# Servotor32.net
KiCad netlist of a schematic drawn in EAGLE
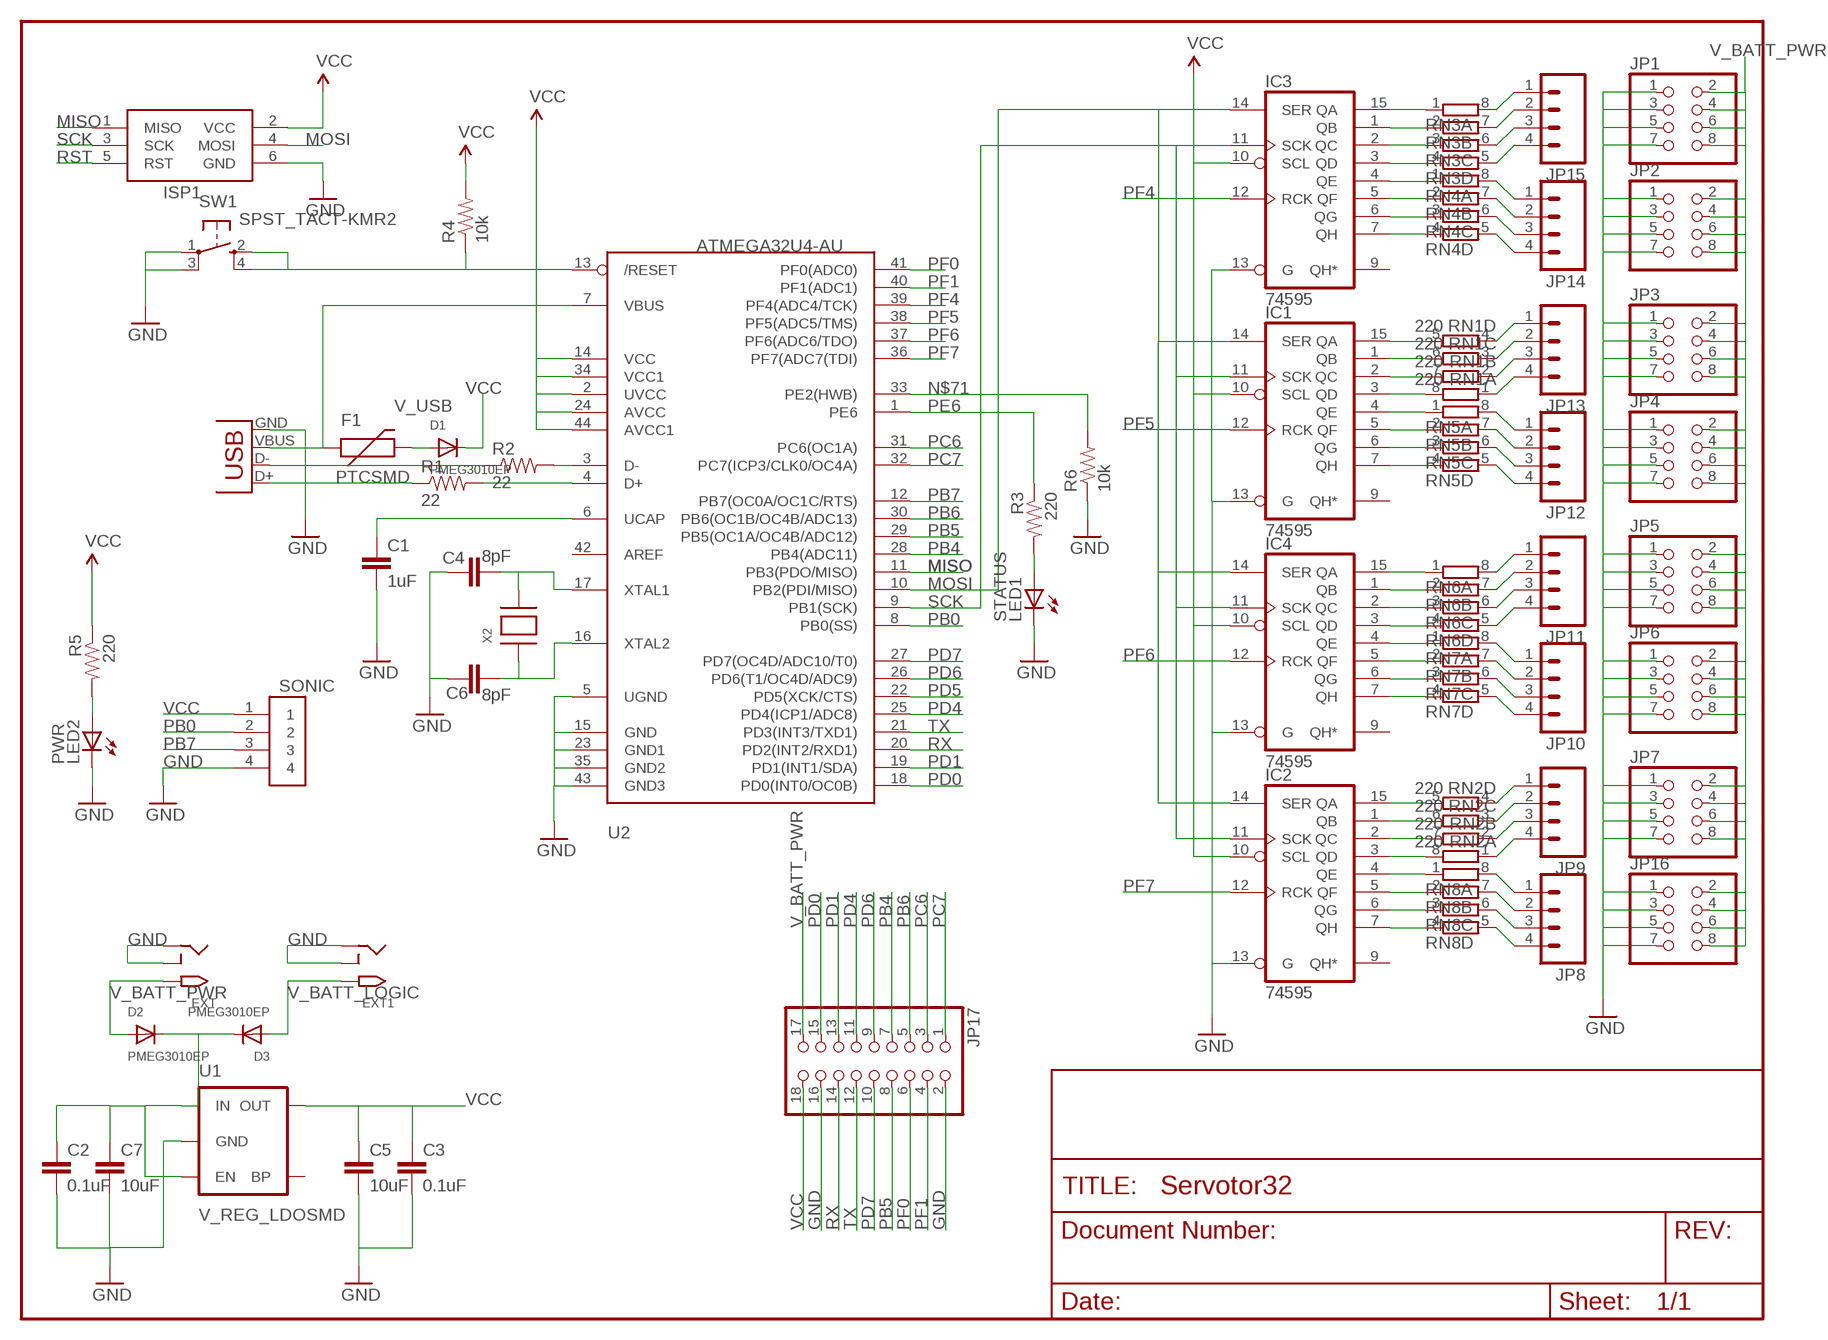
[diagram p0: schematic, sheet 1]

(export (version "E")
  (design (tool "Eeschema 10.0.6"))
  (components
    (comp (ref "C1")
      (value "1uF")
      (footprint "eagle-import:0603-CAP")
      (libsource (lib "eagle-import") (part "CAP0603-CAP"))
    )
    (comp (ref "C2")
      (value "0.1uF")
      (footprint "eagle-import:0603-CAP")
      (libsource (lib "eagle-import") (part "CAP0603-CAP"))
    )
    (comp (ref "C3")
      (value "0.1uF")
      (footprint "eagle-import:0603-CAP")
      (libsource (lib "eagle-import") (part "CAP0603-CAP"))
    )
    (comp (ref "C4")
      (value "8pF")
      (footprint "eagle-import:0603-CAP")
      (libsource (lib "eagle-import") (part "CAP0603-CAP"))
    )
    (comp (ref "C5")
      (value "10uF")
      (footprint "eagle-import:0805")
      (libsource (lib "eagle-import") (part "CAP0805"))
    )
    (comp (ref "C6")
      (value "8pF")
      (footprint "eagle-import:0603-CAP")
      (libsource (lib "eagle-import") (part "CAP0603-CAP"))
    )
    (comp (ref "C7")
      (value "10uF")
      (footprint "eagle-import:0805")
      (libsource (lib "eagle-import") (part "CAP0805"))
    )
    (comp (ref "D1")
      (value "PMEG3010EP")
      (footprint "eagle-import:SOD-128")
      (libsource (lib "eagle-import") (part "PMEG3010EP"))
    )
    (comp (ref "D2")
      (value "PMEG3010EP")
      (footprint "eagle-import:SOD-128")
      (libsource (lib "eagle-import") (part "PMEG3010EP"))
    )
    (comp (ref "D3")
      (value "PMEG3010EP")
      (footprint "eagle-import:SOD-128")
      (libsource (lib "eagle-import") (part "PMEG3010EP"))
    )
    (comp (ref "EXT")
      (value "2.1MMJACKTHM")
      (footprint "eagle-import:PJ-102A")
      (libsource (lib "eagle-import") (part "2.1MMJACKTHM"))
    )
    (comp (ref "EXT1")
      (value "2.1MMJACKTHM")
      (footprint "eagle-import:PJ-102A")
      (libsource (lib "eagle-import") (part "2.1MMJACKTHM"))
    )
    (comp (ref "F1")
      (value "PTCSMD")
      (footprint "eagle-import:PTC-1206")
      (libsource (lib "eagle-import") (part "PTCSMD"))
    )
    (comp (ref "IC1")
      (value "74595")
      (footprint "eagle-import:TSSOP16")
      (libsource (lib "eagle-import") (part "74595"))
    )
    (comp (ref "IC2")
      (value "74595")
      (footprint "eagle-import:TSSOP16")
      (libsource (lib "eagle-import") (part "74595"))
    )
    (comp (ref "IC3")
      (value "74595")
      (footprint "eagle-import:TSSOP16")
      (libsource (lib "eagle-import") (part "74595"))
    )
    (comp (ref "IC4")
      (value "74595")
      (footprint "eagle-import:TSSOP16")
      (libsource (lib "eagle-import") (part "74595"))
    )
    (comp (ref "ISP1")
      (value "AVRISP-6")
      (footprint "eagle-import:AVRISP")
      (libsource (lib "eagle-import") (part "AVRISP-6"))
    )
    (comp (ref "JP1")
      (value "PINHD-2X4")
      (footprint "eagle-import:2X04")
      (libsource (lib "eagle-import") (part "PINHD-2X4"))
    )
    (comp (ref "JP2")
      (value "PINHD-2X4")
      (footprint "eagle-import:2X04")
      (libsource (lib "eagle-import") (part "PINHD-2X4"))
    )
    (comp (ref "JP3")
      (value "PINHD-2X4")
      (footprint "eagle-import:2X04")
      (libsource (lib "eagle-import") (part "PINHD-2X4"))
    )
    (comp (ref "JP4")
      (value "PINHD-2X4")
      (footprint "eagle-import:2X04")
      (libsource (lib "eagle-import") (part "PINHD-2X4"))
    )
    (comp (ref "JP5")
      (value "PINHD-2X4")
      (footprint "eagle-import:2X04")
      (libsource (lib "eagle-import") (part "PINHD-2X4"))
    )
    (comp (ref "JP6")
      (value "PINHD-2X4")
      (footprint "eagle-import:2X04")
      (libsource (lib "eagle-import") (part "PINHD-2X4"))
    )
    (comp (ref "JP7")
      (value "PINHD-2X4")
      (footprint "eagle-import:2X04")
      (libsource (lib "eagle-import") (part "PINHD-2X4"))
    )
    (comp (ref "JP8")
      (value "M04PTH")
      (footprint "eagle-import:1X04")
      (libsource (lib "eagle-import") (part "M04PTH"))
    )
    (comp (ref "JP9")
      (value "M04PTH")
      (footprint "eagle-import:1X04")
      (libsource (lib "eagle-import") (part "M04PTH"))
    )
    (comp (ref "JP10")
      (value "M04PTH")
      (footprint "eagle-import:1X04")
      (libsource (lib "eagle-import") (part "M04PTH"))
    )
    (comp (ref "JP11")
      (value "M04PTH")
      (footprint "eagle-import:1X04")
      (libsource (lib "eagle-import") (part "M04PTH"))
    )
    (comp (ref "JP12")
      (value "M04PTH")
      (footprint "eagle-import:1X04")
      (libsource (lib "eagle-import") (part "M04PTH"))
    )
    (comp (ref "JP13")
      (value "M04PTH")
      (footprint "eagle-import:1X04")
      (libsource (lib "eagle-import") (part "M04PTH"))
    )
    (comp (ref "JP14")
      (value "M04PTH")
      (footprint "eagle-import:1X04")
      (libsource (lib "eagle-import") (part "M04PTH"))
    )
    (comp (ref "JP15")
      (value "M04PTH")
      (footprint "eagle-import:1X04")
      (libsource (lib "eagle-import") (part "M04PTH"))
    )
    (comp (ref "JP16")
      (value "PINHD-2X4")
      (footprint "eagle-import:2X04")
      (libsource (lib "eagle-import") (part "PINHD-2X4"))
    )
    (comp (ref "JP17")
      (value "PINHD-2X9-BIG")
      (footprint "eagle-import:2X09-BIG")
      (libsource (lib "eagle-import") (part "PINHD-2X9-BIG"))
    )
    (comp (ref "LED1")
      (value "STATUS")
      (footprint "eagle-import:SML0805")
      (libsource (lib "eagle-import") (part "LEDSML0805"))
    )
    (comp (ref "LED2")
      (value "PWR")
      (footprint "eagle-import:SML0805")
      (libsource (lib "eagle-import") (part "LEDSML0805"))
    )
    (comp (ref "R1")
      (value "22")
      (footprint "eagle-import:0603-RES")
      (libsource (lib "eagle-import") (part "RESISTOR0603-RES"))
    )
    (comp (ref "R2")
      (value "22")
      (footprint "eagle-import:0603-RES")
      (libsource (lib "eagle-import") (part "RESISTOR0603-RES"))
    )
    (comp (ref "R3")
      (value "220")
      (footprint "eagle-import:0603-RES")
      (libsource (lib "eagle-import") (part "RESISTOR0603-RES"))
    )
    (comp (ref "R4")
      (value "10k")
      (footprint "eagle-import:0603-RES")
      (libsource (lib "eagle-import") (part "RESISTOR0603-RES"))
    )
    (comp (ref "R5")
      (value "220")
      (footprint "eagle-import:0603-RES")
      (libsource (lib "eagle-import") (part "RESISTOR0603-RES"))
    )
    (comp (ref "R6")
      (value "10k")
      (footprint "eagle-import:0603-RES")
      (libsource (lib "eagle-import") (part "RESISTOR0603-RES"))
    )
    (comp (ref "RN1")
      (value "220")
      (footprint "eagle-import:EXB38V")
      (libsource (lib "eagle-import") (part "4R-NEXB38V"))
    )
    (comp (ref "RN2")
      (value "220")
      (footprint "eagle-import:EXB38V")
      (libsource (lib "eagle-import") (part "4R-NEXB38V"))
    )
    (comp (ref "RN3")
      (value "4R-NEXB38V")
      (footprint "eagle-import:EXB38V")
      (libsource (lib "eagle-import") (part "4R-NEXB38V"))
    )
    (comp (ref "RN4")
      (value "4R-NEXB38V")
      (footprint "eagle-import:EXB38V")
      (libsource (lib "eagle-import") (part "4R-NEXB38V"))
    )
    (comp (ref "RN5")
      (value "4R-NEXB38V")
      (footprint "eagle-import:EXB38V")
      (libsource (lib "eagle-import") (part "4R-NEXB38V"))
    )
    (comp (ref "RN6")
      (value "4R-NEXB38V")
      (footprint "eagle-import:EXB38V")
      (libsource (lib "eagle-import") (part "4R-NEXB38V"))
    )
    (comp (ref "RN7")
      (value "4R-NEXB38V")
      (footprint "eagle-import:EXB38V")
      (libsource (lib "eagle-import") (part "4R-NEXB38V"))
    )
    (comp (ref "RN8")
      (value "4R-NEXB38V")
      (footprint "eagle-import:EXB38V")
      (libsource (lib "eagle-import") (part "4R-NEXB38V"))
    )
    (comp (ref "SONIC")
      (value "SONIC")
      (footprint "eagle-import:1X04-BIG")
      (libsource (lib "eagle-import") (part "1X4-BIG"))
    )
    (comp (ref "SW1")
      (value "SPST_TACT-KMR2")
      (footprint "eagle-import:KMR2")
      (libsource (lib "eagle-import") (part "SPST_TACT-KMR2"))
    )
    (comp (ref "U1")
      (value "V_REG_LDOSMD")
      (footprint "eagle-import:SOT23-5")
      (libsource (lib "eagle-import") (part "V_REG_LDOSMD"))
    )
    (comp (ref "U2")
      (value "ATMEGA32U4-AU")
      (footprint "eagle-import:TQFP44")
      (libsource (lib "eagle-import") (part "ATMEGA32U4-AU"))
    )
    (comp (ref "X1")
      (value "USBSMD")
      (footprint "eagle-import:USB-MINIB")
      (libsource (lib "eagle-import") (part "USBSMD"))
    )
    (comp (ref "X2")
      (value "XTALNX5032")
      (footprint "eagle-import:NX5032")
      (libsource (lib "eagle-import") (part "XTALNX5032"))
    )
  )
  (nets
    (net (code "1") (name "/MISO") (class "Default")
      (node (ref "ISP1") (pin "1") (pinfunction "MISO_1") (pintype "input"))
      (node (ref "U2") (pin "11") (pinfunction "PB3(PDO/MISO)_11") (pintype "bidirectional"))
    )
    (net (code "2") (name "/MOSI") (class "Default")
      (node (ref "IC1") (pin "14") (pinfunction "SER_14") (pintype "input"))
      (node (ref "IC2") (pin "14") (pinfunction "SER_14") (pintype "input"))
      (node (ref "IC3") (pin "14") (pinfunction "SER_14") (pintype "input"))
      (node (ref "IC4") (pin "14") (pinfunction "SER_14") (pintype "input"))
      (node (ref "ISP1") (pin "4") (pinfunction "MOSI_4") (pintype "output"))
      (node (ref "U2") (pin "10") (pinfunction "PB2(PDI/MISO)_10") (pintype "bidirectional"))
    )
    (net (code "3") (name "/N$71") (class "Default")
      (node (ref "R6") (pin "2") (pinfunction "2_2") (pintype "passive"))
      (node (ref "U2") (pin "33") (pinfunction "PE2(HWB)_33") (pintype "bidirectional"))
    )
    (net (code "4") (name "/PB0") (class "Default")
      (node (ref "SONIC") (pin "2") (pinfunction "2_2") (pintype "bidirectional"))
      (node (ref "U2") (pin "8") (pinfunction "PB0(SS)_8") (pintype "bidirectional"))
    )
    (net (code "5") (name "/PB4") (class "Default")
      (node (ref "JP17") (pin "7") (pinfunction "7_7") (pintype "passive"))
      (node (ref "U2") (pin "28") (pinfunction "PB4(ADC11)_28") (pintype "bidirectional"))
    )
    (net (code "6") (name "/PB5") (class "Default")
      (node (ref "JP17") (pin "8") (pinfunction "8_8") (pintype "passive"))
      (node (ref "U2") (pin "29") (pinfunction "PB5(OC1A/OC4B/ADC12)_29") (pintype "bidirectional"))
    )
    (net (code "7") (name "/PB6") (class "Default")
      (node (ref "JP17") (pin "5") (pinfunction "5_5") (pintype "passive"))
      (node (ref "U2") (pin "30") (pinfunction "PB6(OC1B/OC4B/ADC13)_30") (pintype "bidirectional"))
    )
    (net (code "8") (name "/PB7") (class "Default")
      (node (ref "SONIC") (pin "3") (pinfunction "3_3") (pintype "bidirectional"))
      (node (ref "U2") (pin "12") (pinfunction "PB7(OC0A/OC1C/RTS)_12") (pintype "bidirectional"))
    )
    (net (code "9") (name "/PC6") (class "Default")
      (node (ref "JP17") (pin "3") (pinfunction "3_3") (pintype "passive"))
      (node (ref "U2") (pin "31") (pinfunction "PC6(OC1A)_31") (pintype "bidirectional"))
    )
    (net (code "10") (name "/PC7") (class "Default")
      (node (ref "JP17") (pin "1") (pinfunction "1_1") (pintype "passive"))
      (node (ref "U2") (pin "32") (pinfunction "PC7(ICP3/CLK0/OC4A)_32") (pintype "bidirectional"))
    )
    (net (code "11") (name "/PD0") (class "Default")
      (node (ref "JP17") (pin "15") (pinfunction "15_15") (pintype "passive"))
      (node (ref "U2") (pin "18") (pinfunction "PD0(INT0/OC0B)_18") (pintype "bidirectional"))
    )
    (net (code "12") (name "/PD1") (class "Default")
      (node (ref "JP17") (pin "13") (pinfunction "13_13") (pintype "passive"))
      (node (ref "U2") (pin "19") (pinfunction "PD1(INT1/SDA)_19") (pintype "bidirectional"))
    )
    (net (code "13") (name "/PD4") (class "Default")
      (node (ref "JP17") (pin "11") (pinfunction "11_11") (pintype "passive"))
      (node (ref "U2") (pin "25") (pinfunction "PD4(ICP1/ADC8)_25") (pintype "bidirectional"))
    )
    (net (code "14") (name "/PD5") (class "Default")
      (node (ref "U2") (pin "22") (pinfunction "PD5(XCK/CTS)_22") (pintype "bidirectional"))
    )
    (net (code "15") (name "/PD6") (class "Default")
      (node (ref "JP17") (pin "9") (pinfunction "9_9") (pintype "passive"))
      (node (ref "U2") (pin "26") (pinfunction "PD6(T1/OC4D/ADC9)_26") (pintype "bidirectional"))
    )
    (net (code "16") (name "/PD7") (class "Default")
      (node (ref "JP17") (pin "10") (pinfunction "10_10") (pintype "passive"))
      (node (ref "U2") (pin "27") (pinfunction "PD7(OC4D/ADC10/T0)_27") (pintype "bidirectional"))
    )
    (net (code "17") (name "/PE6") (class "Default")
      (node (ref "R3") (pin "1") (pinfunction "1_1") (pintype "passive"))
      (node (ref "U2") (pin "1") (pinfunction "PE6_1") (pintype "bidirectional"))
    )
    (net (code "18") (name "/PF0") (class "Default")
      (node (ref "JP17") (pin "6") (pinfunction "6_6") (pintype "passive"))
      (node (ref "U2") (pin "41") (pinfunction "PF0(ADC0)_41") (pintype "bidirectional"))
    )
    (net (code "19") (name "/PF1") (class "Default")
      (node (ref "JP17") (pin "4") (pinfunction "4_4") (pintype "passive"))
      (node (ref "U2") (pin "40") (pinfunction "PF1(ADC1)_40") (pintype "bidirectional"))
    )
    (net (code "20") (name "/PF4") (class "Default")
      (node (ref "IC3") (pin "12") (pinfunction "RCK_12") (pintype "input"))
      (node (ref "U2") (pin "39") (pinfunction "PF4(ADC4/TCK)_39") (pintype "bidirectional"))
    )
    (net (code "21") (name "/PF5") (class "Default")
      (node (ref "IC1") (pin "12") (pinfunction "RCK_12") (pintype "input"))
      (node (ref "U2") (pin "38") (pinfunction "PF5(ADC5/TMS)_38") (pintype "bidirectional"))
    )
    (net (code "22") (name "/PF6") (class "Default")
      (node (ref "IC4") (pin "12") (pinfunction "RCK_12") (pintype "input"))
      (node (ref "U2") (pin "37") (pinfunction "PF6(ADC6/TDO)_37") (pintype "bidirectional"))
    )
    (net (code "23") (name "/PF7") (class "Default")
      (node (ref "IC2") (pin "12") (pinfunction "RCK_12") (pintype "input"))
      (node (ref "U2") (pin "36") (pinfunction "PF7(ADC7(TDI)_36") (pintype "bidirectional"))
    )
    (net (code "24") (name "/RST") (class "Default")
      (node (ref "ISP1") (pin "5") (pinfunction "RST_5") (pintype "output"))
      (node (ref "R4") (pin "1") (pinfunction "1_1") (pintype "passive"))
      (node (ref "SW1") (pin "2") (pinfunction "S_2") (pintype "passive"))
      (node (ref "SW1") (pin "4") (pinfunction "S1_4") (pintype "passive"))
      (node (ref "U2") (pin "13") (pinfunction "/RESET_13") (pintype "bidirectional"))
    )
    (net (code "25") (name "/RX") (class "Default")
      (node (ref "JP17") (pin "14") (pinfunction "14_14") (pintype "passive"))
      (node (ref "U2") (pin "20") (pinfunction "PD2(INT2/RXD1)_20") (pintype "bidirectional"))
    )
    (net (code "26") (name "/SCK") (class "Default")
      (node (ref "IC1") (pin "11") (pinfunction "SCK_11") (pintype "input"))
      (node (ref "IC2") (pin "11") (pinfunction "SCK_11") (pintype "input"))
      (node (ref "IC3") (pin "11") (pinfunction "SCK_11") (pintype "input"))
      (node (ref "IC4") (pin "11") (pinfunction "SCK_11") (pintype "input"))
      (node (ref "ISP1") (pin "3") (pinfunction "SCK_3") (pintype "output"))
      (node (ref "U2") (pin "9") (pinfunction "PB1(SCK)_9") (pintype "bidirectional"))
    )
    (net (code "27") (name "/TX") (class "Default")
      (node (ref "JP17") (pin "12") (pinfunction "12_12") (pintype "passive"))
      (node (ref "U2") (pin "21") (pinfunction "PD3(INT3/TXD1)_21") (pintype "bidirectional"))
    )
    (net (code "28") (name "/V_BATT") (class "Default")
      (node (ref "C2") (pin "1") (pinfunction "1_1") (pintype "passive"))
      (node (ref "C7") (pin "1") (pinfunction "1_1") (pintype "passive"))
      (node (ref "D2") (pin "P$1") (pinfunction "C_P$1") (pintype "passive"))
      (node (ref "D3") (pin "P$1") (pinfunction "C_P$1") (pintype "passive"))
      (node (ref "U1") (pin "1") (pinfunction "IN_1") (pintype "input"))
      (node (ref "U1") (pin "3") (pinfunction "EN_3") (pintype "input"))
    )
    (net (code "29") (name "/V_BATT_LOGIC") (class "Default")
      (node (ref "D3") (pin "P$2") (pinfunction "A_P$2") (pintype "passive"))
      (node (ref "EXT1") (pin "TIP") (pinfunction "TIP_TIP") (pintype "bidirectional"))
    )
    (net (code "30") (name "/V_BATT_PWR") (class "Default")
      (node (ref "D2") (pin "P$2") (pinfunction "A_P$2") (pintype "passive"))
      (node (ref "EXT") (pin "TIP") (pinfunction "TIP_TIP") (pintype "bidirectional"))
      (node (ref "JP1") (pin "2") (pinfunction "2_2") (pintype "passive"))
      (node (ref "JP1") (pin "4") (pinfunction "4_4") (pintype "passive"))
      (node (ref "JP1") (pin "6") (pinfunction "6_6") (pintype "passive"))
      (node (ref "JP1") (pin "8") (pinfunction "8_8") (pintype "passive"))
      (node (ref "JP16") (pin "2") (pinfunction "2_2") (pintype "passive"))
      (node (ref "JP16") (pin "4") (pinfunction "4_4") (pintype "passive"))
      (node (ref "JP16") (pin "6") (pinfunction "6_6") (pintype "passive"))
      (node (ref "JP16") (pin "8") (pinfunction "8_8") (pintype "passive"))
      (node (ref "JP17") (pin "17") (pinfunction "17_17") (pintype "passive"))
      (node (ref "JP2") (pin "2") (pinfunction "2_2") (pintype "passive"))
      (node (ref "JP2") (pin "4") (pinfunction "4_4") (pintype "passive"))
      (node (ref "JP2") (pin "6") (pinfunction "6_6") (pintype "passive"))
      (node (ref "JP2") (pin "8") (pinfunction "8_8") (pintype "passive"))
      (node (ref "JP3") (pin "2") (pinfunction "2_2") (pintype "passive"))
      (node (ref "JP3") (pin "4") (pinfunction "4_4") (pintype "passive"))
      (node (ref "JP3") (pin "6") (pinfunction "6_6") (pintype "passive"))
      (node (ref "JP3") (pin "8") (pinfunction "8_8") (pintype "passive"))
      (node (ref "JP4") (pin "2") (pinfunction "2_2") (pintype "passive"))
      (node (ref "JP4") (pin "4") (pinfunction "4_4") (pintype "passive"))
      (node (ref "JP4") (pin "6") (pinfunction "6_6") (pintype "passive"))
      (node (ref "JP4") (pin "8") (pinfunction "8_8") (pintype "passive"))
      (node (ref "JP5") (pin "2") (pinfunction "2_2") (pintype "passive"))
      (node (ref "JP5") (pin "4") (pinfunction "4_4") (pintype "passive"))
      (node (ref "JP5") (pin "6") (pinfunction "6_6") (pintype "passive"))
      (node (ref "JP5") (pin "8") (pinfunction "8_8") (pintype "passive"))
      (node (ref "JP6") (pin "2") (pinfunction "2_2") (pintype "passive"))
      (node (ref "JP6") (pin "4") (pinfunction "4_4") (pintype "passive"))
      (node (ref "JP6") (pin "6") (pinfunction "6_6") (pintype "passive"))
      (node (ref "JP6") (pin "8") (pinfunction "8_8") (pintype "passive"))
      (node (ref "JP7") (pin "2") (pinfunction "2_2") (pintype "passive"))
      (node (ref "JP7") (pin "4") (pinfunction "4_4") (pintype "passive"))
      (node (ref "JP7") (pin "6") (pinfunction "6_6") (pintype "passive"))
      (node (ref "JP7") (pin "8") (pinfunction "8_8") (pintype "passive"))
    )
    (net (code "31") (name "/V_USB") (class "Default")
      (node (ref "D1") (pin "P$2") (pinfunction "A_P$2") (pintype "passive"))
      (node (ref "F1") (pin "2") (pinfunction "2_2") (pintype "bidirectional"))
    )
    (net (code "32") (name "GND") (class "Default")
      (node (ref "C1") (pin "2") (pinfunction "2_2") (pintype "passive"))
      (node (ref "C2") (pin "2") (pinfunction "2_2") (pintype "passive"))
      (node (ref "C3") (pin "2") (pinfunction "2_2") (pintype "passive"))
      (node (ref "C4") (pin "2") (pinfunction "2_2") (pintype "passive"))
      (node (ref "C5") (pin "2") (pinfunction "2_2") (pintype "passive"))
      (node (ref "C6") (pin "2") (pinfunction "2_2") (pintype "passive"))
      (node (ref "C7") (pin "2") (pinfunction "2_2") (pintype "passive"))
      (node (ref "EXT") (pin "RING") (pinfunction "RING_RING") (pintype "bidirectional"))
      (node (ref "EXT") (pin "RING_SW") (pinfunction "RING_SW_RING_SW") (pintype "bidirectional"))
      (node (ref "EXT1") (pin "RING") (pinfunction "RING_RING") (pintype "bidirectional"))
      (node (ref "EXT1") (pin "RING_SW") (pinfunction "RING_SW_RING_SW") (pintype "bidirectional"))
      (node (ref "IC1") (pin "13") (pinfunction "G_13") (pintype "input"))
      (node (ref "IC2") (pin "13") (pinfunction "G_13") (pintype "input"))
      (node (ref "IC3") (pin "13") (pinfunction "G_13") (pintype "input"))
      (node (ref "IC4") (pin "13") (pinfunction "G_13") (pintype "input"))
      (node (ref "ISP1") (pin "6") (pinfunction "GND_6") (pintype "power_in"))
      (node (ref "JP1") (pin "1") (pinfunction "1_1") (pintype "passive"))
      (node (ref "JP1") (pin "3") (pinfunction "3_3") (pintype "passive"))
      (node (ref "JP1") (pin "5") (pinfunction "5_5") (pintype "passive"))
      (node (ref "JP1") (pin "7") (pinfunction "7_7") (pintype "passive"))
      (node (ref "JP16") (pin "1") (pinfunction "1_1") (pintype "passive"))
      (node (ref "JP16") (pin "3") (pinfunction "3_3") (pintype "passive"))
      (node (ref "JP16") (pin "5") (pinfunction "5_5") (pintype "passive"))
      (node (ref "JP16") (pin "7") (pinfunction "7_7") (pintype "passive"))
      (node (ref "JP17") (pin "16") (pinfunction "16_16") (pintype "passive"))
      (node (ref "JP17") (pin "2") (pinfunction "2_2") (pintype "passive"))
      (node (ref "JP2") (pin "1") (pinfunction "1_1") (pintype "passive"))
      (node (ref "JP2") (pin "3") (pinfunction "3_3") (pintype "passive"))
      (node (ref "JP2") (pin "5") (pinfunction "5_5") (pintype "passive"))
      (node (ref "JP2") (pin "7") (pinfunction "7_7") (pintype "passive"))
      (node (ref "JP3") (pin "1") (pinfunction "1_1") (pintype "passive"))
      (node (ref "JP3") (pin "3") (pinfunction "3_3") (pintype "passive"))
      (node (ref "JP3") (pin "5") (pinfunction "5_5") (pintype "passive"))
      (node (ref "JP3") (pin "7") (pinfunction "7_7") (pintype "passive"))
      (node (ref "JP4") (pin "1") (pinfunction "1_1") (pintype "passive"))
      (node (ref "JP4") (pin "3") (pinfunction "3_3") (pintype "passive"))
      (node (ref "JP4") (pin "5") (pinfunction "5_5") (pintype "passive"))
      (node (ref "JP4") (pin "7") (pinfunction "7_7") (pintype "passive"))
      (node (ref "JP5") (pin "1") (pinfunction "1_1") (pintype "passive"))
      (node (ref "JP5") (pin "3") (pinfunction "3_3") (pintype "passive"))
      (node (ref "JP5") (pin "5") (pinfunction "5_5") (pintype "passive"))
      (node (ref "JP5") (pin "7") (pinfunction "7_7") (pintype "passive"))
      (node (ref "JP6") (pin "1") (pinfunction "1_1") (pintype "passive"))
      (node (ref "JP6") (pin "3") (pinfunction "3_3") (pintype "passive"))
      (node (ref "JP6") (pin "5") (pinfunction "5_5") (pintype "passive"))
      (node (ref "JP6") (pin "7") (pinfunction "7_7") (pintype "passive"))
      (node (ref "JP7") (pin "1") (pinfunction "1_1") (pintype "passive"))
      (node (ref "JP7") (pin "3") (pinfunction "3_3") (pintype "passive"))
      (node (ref "JP7") (pin "5") (pinfunction "5_5") (pintype "passive"))
      (node (ref "JP7") (pin "7") (pinfunction "7_7") (pintype "passive"))
      (node (ref "LED1") (pin "C") (pinfunction "C_C") (pintype "passive"))
      (node (ref "LED2") (pin "C") (pinfunction "C_C") (pintype "passive"))
      (node (ref "R6") (pin "1") (pinfunction "1_1") (pintype "passive"))
      (node (ref "SONIC") (pin "4") (pinfunction "4_4") (pintype "bidirectional"))
      (node (ref "SW1") (pin "1") (pinfunction "P_1") (pintype "passive"))
      (node (ref "SW1") (pin "3") (pinfunction "P1_3") (pintype "passive"))
      (node (ref "U1") (pin "2") (pinfunction "GND_2") (pintype "input"))
      (node (ref "U2") (pin "15") (pinfunction "GND_15") (pintype "bidirectional"))
      (node (ref "U2") (pin "23") (pinfunction "GND1_23") (pintype "bidirectional"))
      (node (ref "U2") (pin "35") (pinfunction "GND2_35") (pintype "bidirectional"))
      (node (ref "U2") (pin "43") (pinfunction "GND3_43") (pintype "bidirectional"))
      (node (ref "U2") (pin "5") (pinfunction "UGND_5") (pintype "bidirectional"))
      (node (ref "X1") (pin "GND") (pinfunction "GND_GND") (pintype "bidirectional"))
    )
    (net (code "33") (name "Net-(IC1A-QA)") (class "Default")
      (node (ref "IC1") (pin "15") (pinfunction "QA_15") (pintype "tri_state"))
      (node (ref "RN1") (pin "5") (pinfunction "2_5") (pintype "passive"))
    )
    (net (code "34") (name "Net-(IC1A-QB)") (class "Default")
      (node (ref "IC1") (pin "1") (pinfunction "QB_1") (pintype "tri_state"))
      (node (ref "RN1") (pin "6") (pinfunction "2_6") (pintype "passive"))
    )
    (net (code "35") (name "Net-(IC1A-QC)") (class "Default")
      (node (ref "IC1") (pin "2") (pinfunction "QC_2") (pintype "tri_state"))
      (node (ref "RN1") (pin "7") (pinfunction "2_7") (pintype "passive"))
    )
    (net (code "36") (name "Net-(IC1A-QD)") (class "Default")
      (node (ref "IC1") (pin "3") (pinfunction "QD_3") (pintype "tri_state"))
      (node (ref "RN1") (pin "8") (pinfunction "2_8") (pintype "passive"))
    )
    (net (code "37") (name "Net-(IC1A-QE)") (class "Default")
      (node (ref "IC1") (pin "4") (pinfunction "QE_4") (pintype "tri_state"))
      (node (ref "RN5") (pin "1") (pinfunction "1_1") (pintype "passive"))
    )
    (net (code "38") (name "Net-(IC1A-QF)") (class "Default")
      (node (ref "IC1") (pin "5") (pinfunction "QF_5") (pintype "tri_state"))
      (node (ref "RN5") (pin "2") (pinfunction "1_2") (pintype "passive"))
    )
    (net (code "39") (name "Net-(IC1A-QG)") (class "Default")
      (node (ref "IC1") (pin "6") (pinfunction "QG_6") (pintype "tri_state"))
      (node (ref "RN5") (pin "3") (pinfunction "1_3") (pintype "passive"))
    )
    (net (code "40") (name "Net-(IC1A-QH)") (class "Default")
      (node (ref "IC1") (pin "7") (pinfunction "QH_7") (pintype "tri_state"))
      (node (ref "RN5") (pin "4") (pinfunction "1_4") (pintype "passive"))
    )
    (net (code "41") (name "Net-(IC2A-QA)") (class "Default")
      (node (ref "IC2") (pin "15") (pinfunction "QA_15") (pintype "tri_state"))
      (node (ref "RN2") (pin "5") (pinfunction "2_5") (pintype "passive"))
    )
    (net (code "42") (name "Net-(IC2A-QB)") (class "Default")
      (node (ref "IC2") (pin "1") (pinfunction "QB_1") (pintype "tri_state"))
      (node (ref "RN2") (pin "6") (pinfunction "2_6") (pintype "passive"))
    )
    (net (code "43") (name "Net-(IC2A-QC)") (class "Default")
      (node (ref "IC2") (pin "2") (pinfunction "QC_2") (pintype "tri_state"))
      (node (ref "RN2") (pin "7") (pinfunction "2_7") (pintype "passive"))
    )
    (net (code "44") (name "Net-(IC2A-QD)") (class "Default")
      (node (ref "IC2") (pin "3") (pinfunction "QD_3") (pintype "tri_state"))
      (node (ref "RN2") (pin "8") (pinfunction "2_8") (pintype "passive"))
    )
    (net (code "45") (name "Net-(IC2A-QE)") (class "Default")
      (node (ref "IC2") (pin "4") (pinfunction "QE_4") (pintype "tri_state"))
      (node (ref "RN8") (pin "1") (pinfunction "1_1") (pintype "passive"))
    )
    (net (code "46") (name "Net-(IC2A-QF)") (class "Default")
      (node (ref "IC2") (pin "5") (pinfunction "QF_5") (pintype "tri_state"))
      (node (ref "RN8") (pin "2") (pinfunction "1_2") (pintype "passive"))
    )
    (net (code "47") (name "Net-(IC2A-QG)") (class "Default")
      (node (ref "IC2") (pin "6") (pinfunction "QG_6") (pintype "tri_state"))
      (node (ref "RN8") (pin "3") (pinfunction "1_3") (pintype "passive"))
    )
    (net (code "48") (name "Net-(IC2A-QH)") (class "Default")
      (node (ref "IC2") (pin "7") (pinfunction "QH_7") (pintype "tri_state"))
      (node (ref "RN8") (pin "4") (pinfunction "1_4") (pintype "passive"))
    )
    (net (code "49") (name "Net-(IC3A-QA)") (class "Default")
      (node (ref "IC3") (pin "15") (pinfunction "QA_15") (pintype "tri_state"))
      (node (ref "RN3") (pin "1") (pinfunction "1_1") (pintype "passive"))
    )
    (net (code "50") (name "Net-(IC3A-QB)") (class "Default")
      (node (ref "IC3") (pin "1") (pinfunction "QB_1") (pintype "tri_state"))
      (node (ref "RN3") (pin "2") (pinfunction "1_2") (pintype "passive"))
    )
    (net (code "51") (name "Net-(IC3A-QC)") (class "Default")
      (node (ref "IC3") (pin "2") (pinfunction "QC_2") (pintype "tri_state"))
      (node (ref "RN3") (pin "3") (pinfunction "1_3") (pintype "passive"))
    )
    (net (code "52") (name "Net-(IC3A-QD)") (class "Default")
      (node (ref "IC3") (pin "3") (pinfunction "QD_3") (pintype "tri_state"))
      (node (ref "RN3") (pin "4") (pinfunction "1_4") (pintype "passive"))
    )
    (net (code "53") (name "Net-(IC3A-QE)") (class "Default")
      (node (ref "IC3") (pin "4") (pinfunction "QE_4") (pintype "tri_state"))
      (node (ref "RN4") (pin "1") (pinfunction "1_1") (pintype "passive"))
    )
    (net (code "54") (name "Net-(IC3A-QF)") (class "Default")
      (node (ref "IC3") (pin "5") (pinfunction "QF_5") (pintype "tri_state"))
      (node (ref "RN4") (pin "2") (pinfunction "1_2") (pintype "passive"))
    )
    (net (code "55") (name "Net-(IC3A-QG)") (class "Default")
      (node (ref "IC3") (pin "6") (pinfunction "QG_6") (pintype "tri_state"))
      (node (ref "RN4") (pin "3") (pinfunction "1_3") (pintype "passive"))
    )
    (net (code "56") (name "Net-(IC3A-QH)") (class "Default")
      (node (ref "IC3") (pin "7") (pinfunction "QH_7") (pintype "tri_state"))
      (node (ref "RN4") (pin "4") (pinfunction "1_4") (pintype "passive"))
    )
    (net (code "57") (name "Net-(IC4A-QA)") (class "Default")
      (node (ref "IC4") (pin "15") (pinfunction "QA_15") (pintype "tri_state"))
      (node (ref "RN6") (pin "1") (pinfunction "1_1") (pintype "passive"))
    )
    (net (code "58") (name "Net-(IC4A-QB)") (class "Default")
      (node (ref "IC4") (pin "1") (pinfunction "QB_1") (pintype "tri_state"))
      (node (ref "RN6") (pin "2") (pinfunction "1_2") (pintype "passive"))
    )
    (net (code "59") (name "Net-(IC4A-QC)") (class "Default")
      (node (ref "IC4") (pin "2") (pinfunction "QC_2") (pintype "tri_state"))
      (node (ref "RN6") (pin "3") (pinfunction "1_3") (pintype "passive"))
    )
    (net (code "60") (name "Net-(IC4A-QD)") (class "Default")
      (node (ref "IC4") (pin "3") (pinfunction "QD_3") (pintype "tri_state"))
      (node (ref "RN6") (pin "4") (pinfunction "1_4") (pintype "passive"))
    )
    (net (code "61") (name "Net-(IC4A-QE)") (class "Default")
      (node (ref "IC4") (pin "4") (pinfunction "QE_4") (pintype "tri_state"))
      (node (ref "RN7") (pin "1") (pinfunction "1_1") (pintype "passive"))
    )
    (net (code "62") (name "Net-(IC4A-QF)") (class "Default")
      (node (ref "IC4") (pin "5") (pinfunction "QF_5") (pintype "tri_state"))
      (node (ref "RN7") (pin "2") (pinfunction "1_2") (pintype "passive"))
    )
    (net (code "63") (name "Net-(IC4A-QG)") (class "Default")
      (node (ref "IC4") (pin "6") (pinfunction "QG_6") (pintype "tri_state"))
      (node (ref "RN7") (pin "3") (pinfunction "1_3") (pintype "passive"))
    )
    (net (code "64") (name "Net-(IC4A-QH)") (class "Default")
      (node (ref "IC4") (pin "7") (pinfunction "QH_7") (pintype "tri_state"))
      (node (ref "RN7") (pin "4") (pinfunction "1_4") (pintype "passive"))
    )
    (net (code "65") (name "Net-(JP9-Pad4)") (class "Default")
      (node (ref "JP9") (pin "4") (pinfunction "4_4") (pintype "passive"))
      (node (ref "RN2") (pin "1") (pinfunction "1_1") (pintype "passive"))
    )
    (net (code "66") (name "Net-(JP13-Pad4)") (class "Default")
      (node (ref "JP13") (pin "4") (pinfunction "4_4") (pintype "passive"))
      (node (ref "RN1") (pin "1") (pinfunction "1_1") (pintype "passive"))
    )
    (net (code "67") (name "Net-(LED1-PadA)") (class "Default")
      (node (ref "LED1") (pin "A") (pinfunction "A_A") (pintype "passive"))
      (node (ref "R3") (pin "2") (pinfunction "2_2") (pintype "passive"))
    )
    (net (code "68") (name "Net-(LED2-PadA)") (class "Default")
      (node (ref "LED2") (pin "A") (pinfunction "A_A") (pintype "passive"))
      (node (ref "R5") (pin "2") (pinfunction "2_2") (pintype "passive"))
    )
    (net (code "69") (name "Net-(R1-Pad1)") (class "Default")
      (node (ref "R1") (pin "1") (pinfunction "1_1") (pintype "passive"))
      (node (ref "X1") (pin "D+") (pinfunction "D+_D+") (pintype "bidirectional"))
    )
    (net (code "70") (name "Net-(R2-Pad1)") (class "Default")
      (node (ref "R2") (pin "1") (pinfunction "1_1") (pintype "passive"))
      (node (ref "X1") (pin "D-") (pinfunction "D-_D-") (pintype "bidirectional"))
    )
    (net (code "71") (name "Net-(RN1B-1)") (class "Default")
      (node (ref "JP13") (pin "3") (pinfunction "3_3") (pintype "passive"))
      (node (ref "RN1") (pin "2") (pinfunction "1_2") (pintype "passive"))
    )
    (net (code "72") (name "Net-(RN1C-1)") (class "Default")
      (node (ref "JP13") (pin "2") (pinfunction "2_2") (pintype "passive"))
      (node (ref "RN1") (pin "3") (pinfunction "1_3") (pintype "passive"))
    )
    (net (code "73") (name "Net-(RN1D-1)") (class "Default")
      (node (ref "JP13") (pin "1") (pinfunction "1_1") (pintype "passive"))
      (node (ref "RN1") (pin "4") (pinfunction "1_4") (pintype "passive"))
    )
    (net (code "74") (name "Net-(RN2B-1)") (class "Default")
      (node (ref "JP9") (pin "3") (pinfunction "3_3") (pintype "passive"))
      (node (ref "RN2") (pin "2") (pinfunction "1_2") (pintype "passive"))
    )
    (net (code "75") (name "Net-(RN2C-1)") (class "Default")
      (node (ref "JP9") (pin "2") (pinfunction "2_2") (pintype "passive"))
      (node (ref "RN2") (pin "3") (pinfunction "1_3") (pintype "passive"))
    )
    (net (code "76") (name "Net-(RN2D-1)") (class "Default")
      (node (ref "JP9") (pin "1") (pinfunction "1_1") (pintype "passive"))
      (node (ref "RN2") (pin "4") (pinfunction "1_4") (pintype "passive"))
    )
    (net (code "77") (name "Net-(RN3A-2)") (class "Default")
      (node (ref "JP15") (pin "1") (pinfunction "1_1") (pintype "passive"))
      (node (ref "RN3") (pin "8") (pinfunction "2_8") (pintype "passive"))
    )
    (net (code "78") (name "Net-(RN3B-2)") (class "Default")
      (node (ref "JP15") (pin "2") (pinfunction "2_2") (pintype "passive"))
      (node (ref "RN3") (pin "7") (pinfunction "2_7") (pintype "passive"))
    )
    (net (code "79") (name "Net-(RN3C-2)") (class "Default")
      (node (ref "JP15") (pin "3") (pinfunction "3_3") (pintype "passive"))
      (node (ref "RN3") (pin "6") (pinfunction "2_6") (pintype "passive"))
    )
    (net (code "80") (name "Net-(RN3D-2)") (class "Default")
      (node (ref "JP15") (pin "4") (pinfunction "4_4") (pintype "passive"))
      (node (ref "RN3") (pin "5") (pinfunction "2_5") (pintype "passive"))
    )
    (net (code "81") (name "Net-(RN4A-2)") (class "Default")
      (node (ref "JP14") (pin "1") (pinfunction "1_1") (pintype "passive"))
      (node (ref "RN4") (pin "8") (pinfunction "2_8") (pintype "passive"))
    )
    (net (code "82") (name "Net-(RN4B-2)") (class "Default")
      (node (ref "JP14") (pin "2") (pinfunction "2_2") (pintype "passive"))
      (node (ref "RN4") (pin "7") (pinfunction "2_7") (pintype "passive"))
    )
    (net (code "83") (name "Net-(RN4C-2)") (class "Default")
      (node (ref "JP14") (pin "3") (pinfunction "3_3") (pintype "passive"))
      (node (ref "RN4") (pin "6") (pinfunction "2_6") (pintype "passive"))
    )
    (net (code "84") (name "Net-(RN4D-2)") (class "Default")
      (node (ref "JP14") (pin "4") (pinfunction "4_4") (pintype "passive"))
      (node (ref "RN4") (pin "5") (pinfunction "2_5") (pintype "passive"))
    )
    (net (code "85") (name "Net-(RN5A-2)") (class "Default")
      (node (ref "JP12") (pin "1") (pinfunction "1_1") (pintype "passive"))
      (node (ref "RN5") (pin "8") (pinfunction "2_8") (pintype "passive"))
    )
    (net (code "86") (name "Net-(RN5B-2)") (class "Default")
      (node (ref "JP12") (pin "2") (pinfunction "2_2") (pintype "passive"))
      (node (ref "RN5") (pin "7") (pinfunction "2_7") (pintype "passive"))
    )
    (net (code "87") (name "Net-(RN5C-2)") (class "Default")
      (node (ref "JP12") (pin "3") (pinfunction "3_3") (pintype "passive"))
      (node (ref "RN5") (pin "6") (pinfunction "2_6") (pintype "passive"))
    )
    (net (code "88") (name "Net-(RN5D-2)") (class "Default")
      (node (ref "JP12") (pin "4") (pinfunction "4_4") (pintype "passive"))
      (node (ref "RN5") (pin "5") (pinfunction "2_5") (pintype "passive"))
    )
    (net (code "89") (name "Net-(RN6A-2)") (class "Default")
      (node (ref "JP11") (pin "1") (pinfunction "1_1") (pintype "passive"))
      (node (ref "RN6") (pin "8") (pinfunction "2_8") (pintype "passive"))
    )
    (net (code "90") (name "Net-(RN6B-2)") (class "Default")
      (node (ref "JP11") (pin "2") (pinfunction "2_2") (pintype "passive"))
      (node (ref "RN6") (pin "7") (pinfunction "2_7") (pintype "passive"))
    )
    (net (code "91") (name "Net-(RN6C-2)") (class "Default")
      (node (ref "JP11") (pin "3") (pinfunction "3_3") (pintype "passive"))
      (node (ref "RN6") (pin "6") (pinfunction "2_6") (pintype "passive"))
    )
    (net (code "92") (name "Net-(RN6D-2)") (class "Default")
      (node (ref "JP11") (pin "4") (pinfunction "4_4") (pintype "passive"))
      (node (ref "RN6") (pin "5") (pinfunction "2_5") (pintype "passive"))
    )
    (net (code "93") (name "Net-(RN7A-2)") (class "Default")
      (node (ref "JP10") (pin "1") (pinfunction "1_1") (pintype "passive"))
      (node (ref "RN7") (pin "8") (pinfunction "2_8") (pintype "passive"))
    )
    (net (code "94") (name "Net-(RN7B-2)") (class "Default")
      (node (ref "JP10") (pin "2") (pinfunction "2_2") (pintype "passive"))
      (node (ref "RN7") (pin "7") (pinfunction "2_7") (pintype "passive"))
    )
    (net (code "95") (name "Net-(RN7C-2)") (class "Default")
      (node (ref "JP10") (pin "3") (pinfunction "3_3") (pintype "passive"))
      (node (ref "RN7") (pin "6") (pinfunction "2_6") (pintype "passive"))
    )
    (net (code "96") (name "Net-(RN7D-2)") (class "Default")
      (node (ref "JP10") (pin "4") (pinfunction "4_4") (pintype "passive"))
      (node (ref "RN7") (pin "5") (pinfunction "2_5") (pintype "passive"))
    )
    (net (code "97") (name "Net-(RN8A-2)") (class "Default")
      (node (ref "JP8") (pin "1") (pinfunction "1_1") (pintype "passive"))
      (node (ref "RN8") (pin "8") (pinfunction "2_8") (pintype "passive"))
    )
    (net (code "98") (name "Net-(RN8B-2)") (class "Default")
      (node (ref "JP8") (pin "2") (pinfunction "2_2") (pintype "passive"))
      (node (ref "RN8") (pin "7") (pinfunction "2_7") (pintype "passive"))
    )
    (net (code "99") (name "Net-(RN8C-2)") (class "Default")
      (node (ref "JP8") (pin "3") (pinfunction "3_3") (pintype "passive"))
      (node (ref "RN8") (pin "6") (pinfunction "2_6") (pintype "passive"))
    )
    (net (code "100") (name "Net-(RN8D-2)") (class "Default")
      (node (ref "JP8") (pin "4") (pinfunction "4_4") (pintype "passive"))
      (node (ref "RN8") (pin "5") (pinfunction "2_5") (pintype "passive"))
    )
    (net (code "101") (name "Net-(U2-D+)") (class "Default")
      (node (ref "R1") (pin "2") (pinfunction "2_2") (pintype "passive"))
      (node (ref "U2") (pin "4") (pinfunction "D+_4") (pintype "bidirectional"))
    )
    (net (code "102") (name "Net-(U2-D-)") (class "Default")
      (node (ref "R2") (pin "2") (pinfunction "2_2") (pintype "passive"))
      (node (ref "U2") (pin "3") (pinfunction "D-_3") (pintype "bidirectional"))
    )
    (net (code "103") (name "Net-(U2-UCAP)") (class "Default")
      (node (ref "C1") (pin "1") (pinfunction "1_1") (pintype "passive"))
      (node (ref "U2") (pin "6") (pinfunction "UCAP_6") (pintype "bidirectional"))
    )
    (net (code "104") (name "Net-(U2-VBUS)") (class "Default")
      (node (ref "F1") (pin "1") (pinfunction "1_1") (pintype "bidirectional"))
      (node (ref "U2") (pin "7") (pinfunction "VBUS_7") (pintype "bidirectional"))
      (node (ref "X1") (pin "VBUS") (pinfunction "VBUS_VBUS") (pintype "bidirectional"))
    )
    (net (code "105") (name "Net-(U2-XTAL1)") (class "Default")
      (node (ref "C4") (pin "1") (pinfunction "1_1") (pintype "passive"))
      (node (ref "U2") (pin "17") (pinfunction "XTAL1_17") (pintype "bidirectional"))
      (node (ref "X2") (pin "P$2") (pinfunction "P$2_P$2") (pintype "bidirectional"))
    )
    (net (code "106") (name "Net-(U2-XTAL2)") (class "Default")
      (node (ref "C6") (pin "1") (pinfunction "1_1") (pintype "passive"))
      (node (ref "U2") (pin "16") (pinfunction "XTAL2_16") (pintype "bidirectional"))
      (node (ref "X2") (pin "P$1") (pinfunction "P$1_P$1") (pintype "bidirectional"))
    )
    (net (code "107") (name "VCC") (class "Default")
      (node (ref "C3") (pin "1") (pinfunction "1_1") (pintype "passive"))
      (node (ref "C5") (pin "1") (pinfunction "1_1") (pintype "passive"))
      (node (ref "D1") (pin "P$1") (pinfunction "C_P$1") (pintype "passive"))
      (node (ref "IC1") (pin "10") (pinfunction "SCL_10") (pintype "input"))
      (node (ref "IC2") (pin "10") (pinfunction "SCL_10") (pintype "input"))
      (node (ref "IC3") (pin "10") (pinfunction "SCL_10") (pintype "input"))
      (node (ref "IC4") (pin "10") (pinfunction "SCL_10") (pintype "input"))
      (node (ref "ISP1") (pin "2") (pinfunction "VCC_2") (pintype "power_in"))
      (node (ref "JP17") (pin "18") (pinfunction "18_18") (pintype "passive"))
      (node (ref "R4") (pin "2") (pinfunction "2_2") (pintype "passive"))
      (node (ref "R5") (pin "1") (pinfunction "1_1") (pintype "passive"))
      (node (ref "SONIC") (pin "1") (pinfunction "1_1") (pintype "bidirectional"))
      (node (ref "U1") (pin "5") (pinfunction "OUT_5") (pintype "passive"))
      (node (ref "U2") (pin "14") (pinfunction "VCC_14") (pintype "bidirectional"))
      (node (ref "U2") (pin "2") (pinfunction "UVCC_2") (pintype "bidirectional"))
      (node (ref "U2") (pin "24") (pinfunction "AVCC_24") (pintype "bidirectional"))
      (node (ref "U2") (pin "34") (pinfunction "VCC1_34") (pintype "bidirectional"))
      (node (ref "U2") (pin "44") (pinfunction "AVCC1_44") (pintype "bidirectional"))
    )
    (net (code "108") (name "unconnected-(IC1A-QH*-Pad9)") (class "Default")
      (node (ref "IC1") (pin "9") (pinfunction "QH*_9") (pintype "tri_state"))
    )
    (net (code "109") (name "unconnected-(IC2A-QH*-Pad9)") (class "Default")
      (node (ref "IC2") (pin "9") (pinfunction "QH*_9") (pintype "tri_state"))
    )
    (net (code "110") (name "unconnected-(IC3A-QH*-Pad9)") (class "Default")
      (node (ref "IC3") (pin "9") (pinfunction "QH*_9") (pintype "tri_state"))
    )
    (net (code "111") (name "unconnected-(IC4A-QH*-Pad9)") (class "Default")
      (node (ref "IC4") (pin "9") (pinfunction "QH*_9") (pintype "tri_state"))
    )
    (net (code "112") (name "unconnected-(U1-BP-Pad4)") (class "Default")
      (node (ref "U1") (pin "4") (pinfunction "BP_4") (pintype "input"))
    )
    (net (code "113") (name "unconnected-(U2-AREF-Pad42)") (class "Default")
      (node (ref "U2") (pin "42") (pinfunction "AREF_42") (pintype "bidirectional"))
    )
  )
)
